# Hydrogen_Rocket.net
KiCad netlist of a schematic drawn in EasyEDA
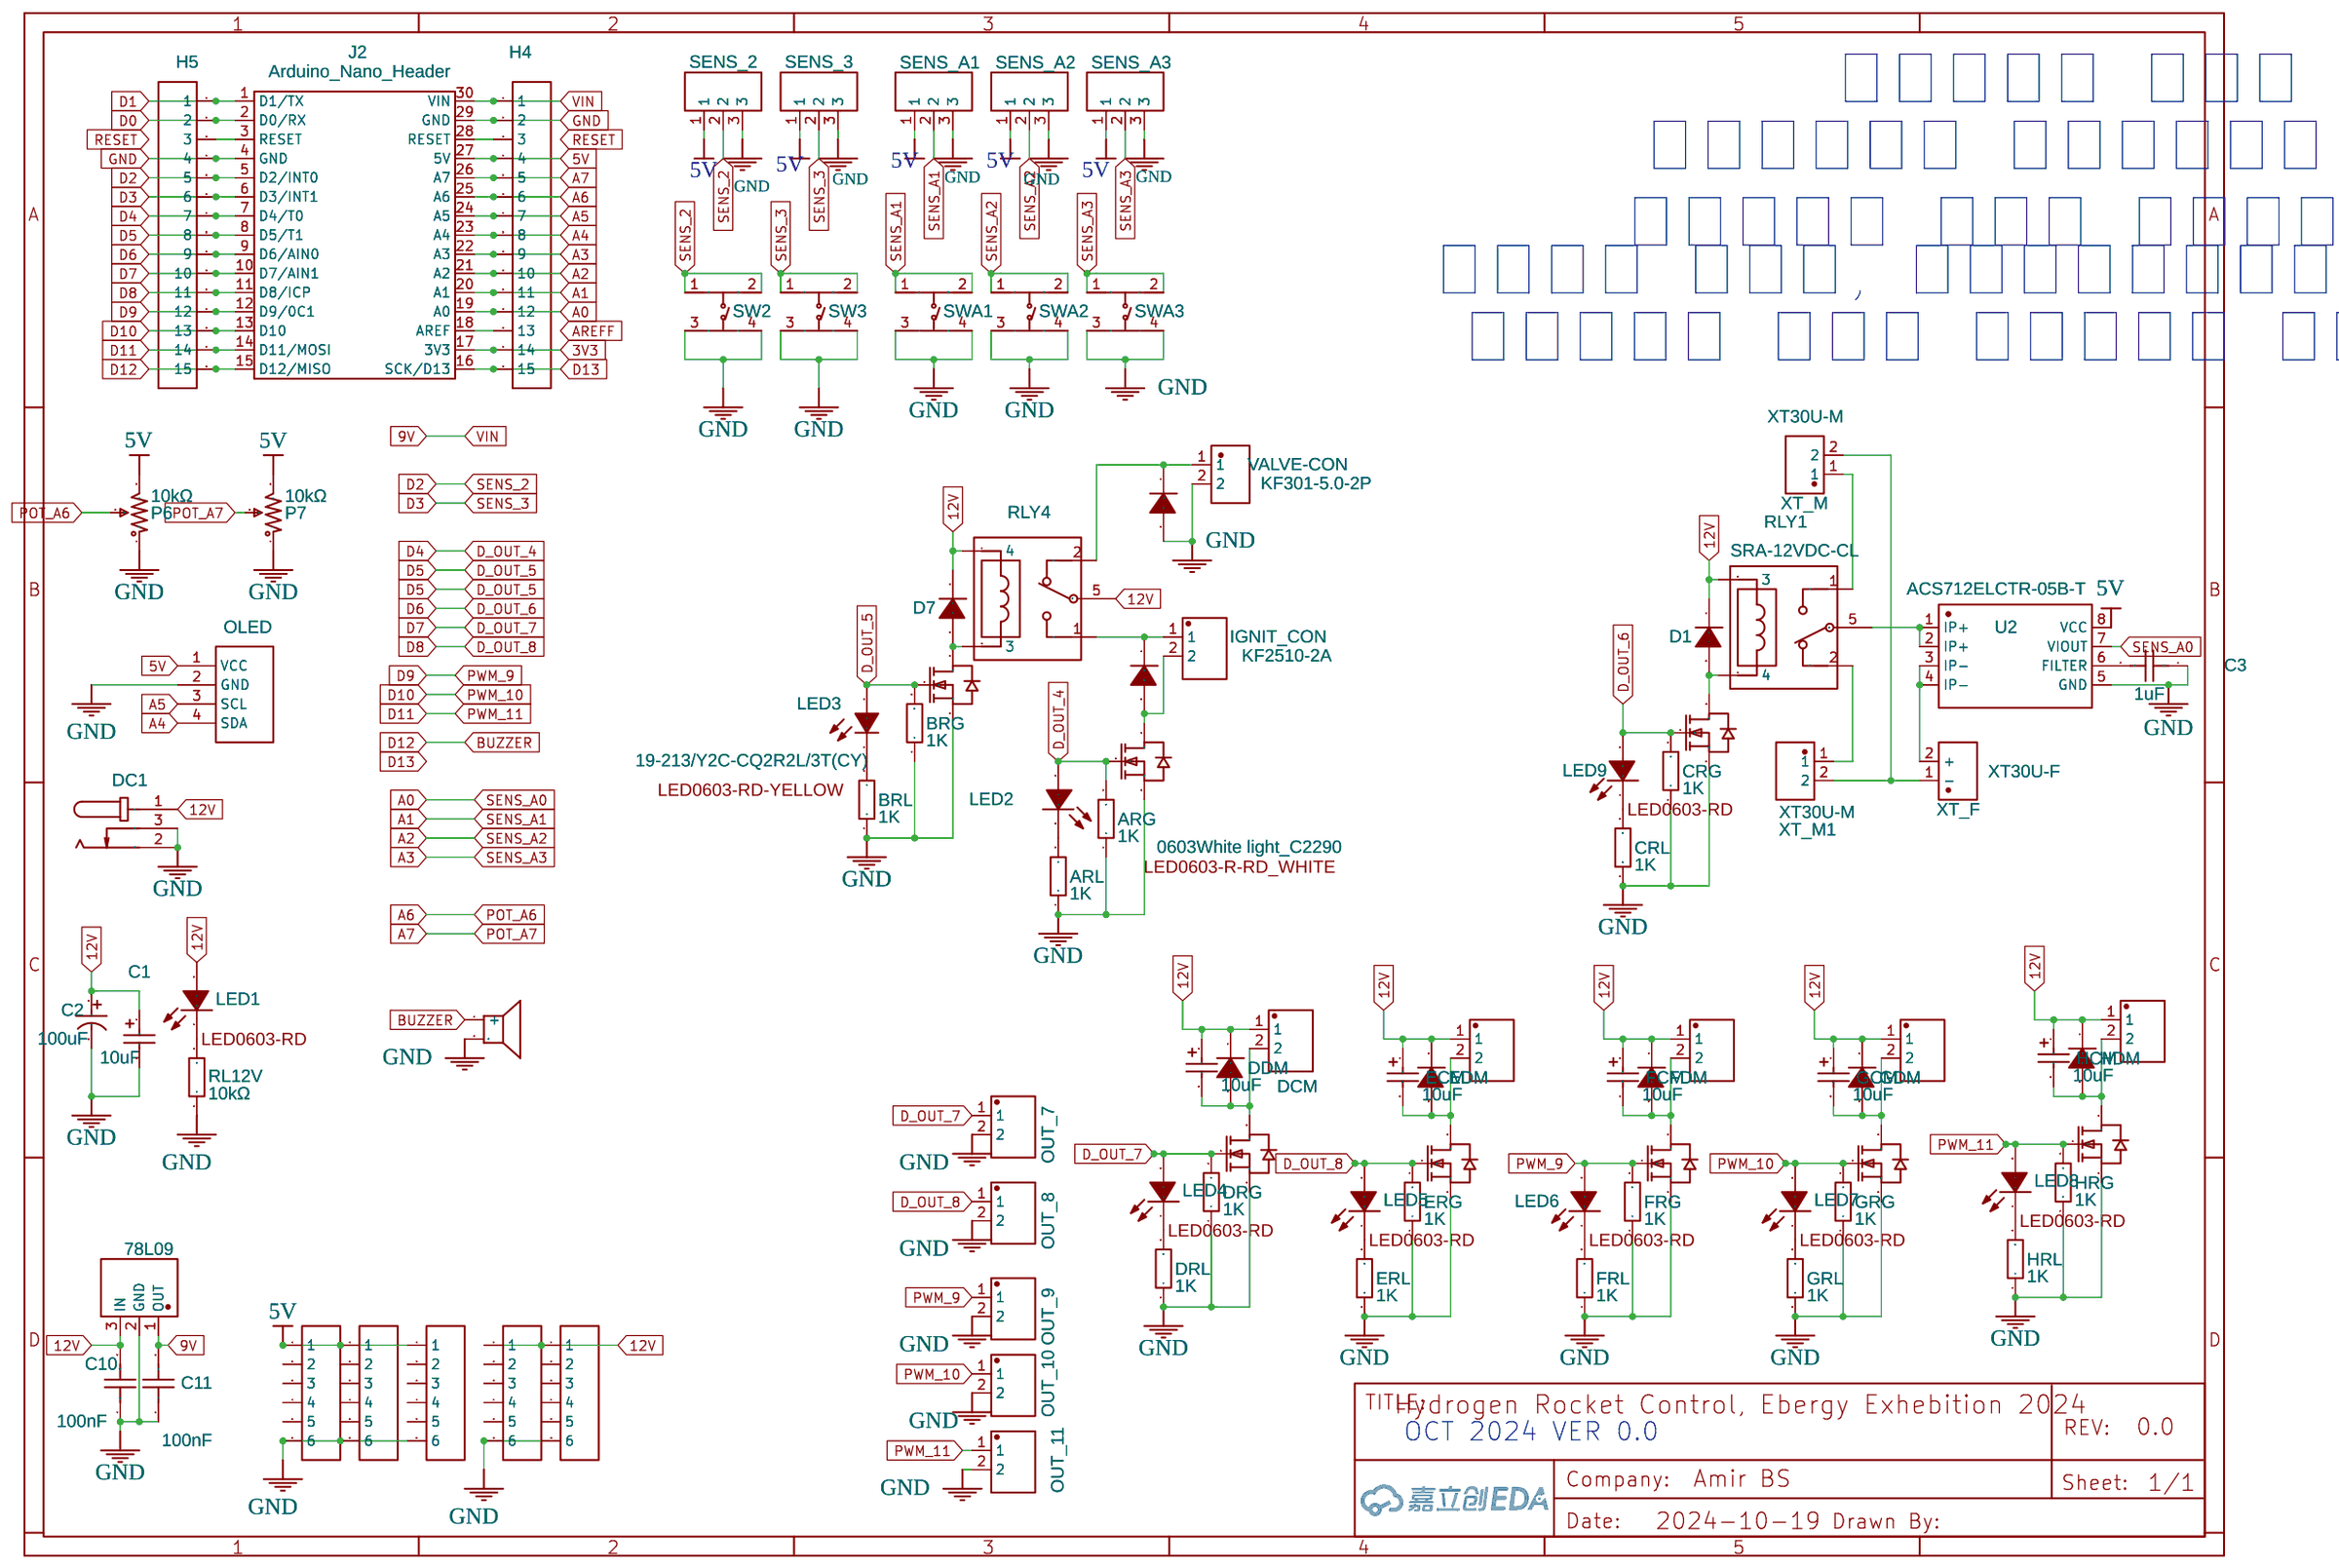
[diagram p0: schematic sheet]

(export (version "E")
  (design (tool "Eeschema 10.0.6"))
  (components
    (comp (ref "AQ")
      (value "Q")
      (fields (field (name "BOM_Manufacturer Part") "AO3400") (field (name "BOM_Supplier Part") "C5224189"))
      (libsource (lib "") (part "JSM2302_4"))
    )
    (comp (ref "ARG")
      (value "1K")
      (fields
        (field (name "BOM_Manufacturer Part") "0603WAF1001T5E")
        (field (name "BOM_Supplier Part") "C21190")
      )
      (libsource (lib "") (part "0603WAF1001T5E_7"))
    )
    (comp (ref "ARL")
      (value "1K")
      (fields
        (field (name "BOM_Manufacturer Part") "0603WAF1001T5E")
        (field (name "BOM_Supplier Part") "C21190")
      )
      (libsource (lib "") (part "0603WAF1001T5E_15"))
    )
    (comp (ref "BQ")
      (value "Q")
      (fields (field (name "BOM_Manufacturer Part") "AO3400") (field (name "BOM_Supplier Part") "C5224189"))
      (libsource (lib "") (part "JSM2302_6"))
    )
    (comp (ref "BRG")
      (value "1K")
      (fields
        (field (name "BOM_Manufacturer Part") "0603WAF1001T5E")
        (field (name "BOM_Supplier Part") "C21190")
      )
      (libsource (lib "") (part "0603WAF1001T5E_2"))
    )
    (comp (ref "BRL")
      (value "1K")
      (fields
        (field (name "BOM_Manufacturer Part") "0603WAF1001T5E")
        (field (name "BOM_Supplier Part") "C21190")
      )
      (libsource (lib "") (part "0603WAF1001T5E_11"))
    )
    (comp (ref "BUZZER1")
      (value "BUZZER-12X9")
      (fields (field (name "Manufacturer Part") "buzzer-12X9"))
      (libsource (lib "") (part "BUZZER-12X9"))
    )
    (comp (ref "C1")
      (value "10uF")
      (fields (field (name "Manufacturer Part") "TAJA106K016RNJ") (field (name "Manufacturer") "Kyocera AVX"))
      (libsource (lib "") (part "TAJA106K016RNJ_4"))
    )
    (comp (ref "C2")
      (value "100uF")
      (fields
        (field (name "Manufacturer Part") "KM107M035E11RR0VH2FP0")
        (field (name "Manufacturer") "CX(承兴)")
      )
      (libsource (lib "") (part "100uF 35V 6.3*11"))
    )
    (comp (ref "C3")
      (value "1uF")
      (fields
        (field (name "Manufacturer Part") "CL10A105KB8NNNC")
        (field (name "Manufacturer") "SAMSUNG(三星)")
      )
      (libsource (lib "") (part "CL10A105KB8NNNC"))
    )
    (comp (ref "C10")
      (value "100nF")
      (fields
        (field (name "Manufacturer Part") "CC0603KRX7R9BB104")
        (field (name "Manufacturer") "YAGEO(国巨)")
      )
      (libsource (lib "") (part "CC0603KRX7R9BB104"))
    )
    (comp (ref "C11")
      (value "100nF")
      (fields
        (field (name "Manufacturer Part") "CC0603KRX7R9BB104")
        (field (name "Manufacturer") "YAGEO(国巨)")
      )
      (libsource (lib "") (part "CC0603KRX7R9BB104"))
    )
    (comp (ref "CQ")
      (value "Q")
      (fields (field (name "BOM_Manufacturer Part") "AO3400") (field (name "BOM_Supplier Part") "C5224189"))
      (libsource (lib "") (part "JSM2302_3"))
    )
    (comp (ref "CRG")
      (value "1K")
      (fields
        (field (name "BOM_Manufacturer Part") "0603WAF1001T5E")
        (field (name "BOM_Supplier Part") "C21190")
      )
      (libsource (lib "") (part "0603WAF1001T5E_10"))
    )
    (comp (ref "CRL")
      (value "1K")
      (fields
        (field (name "BOM_Manufacturer Part") "0603WAF1001T5E")
        (field (name "BOM_Supplier Part") "C21190")
      )
      (libsource (lib "") (part "0603WAF1001T5E_3"))
    )
    (comp (ref "D1")
      (value "M7_C95872")
      (fields (field (name "Manufacturer Part") "M7") (field (name "Manufacturer") "MDD"))
      (libsource (lib "") (part "M7_C95872"))
    )
    (comp (ref "D7")
      (value "M7_C95872")
      (fields (field (name "Manufacturer Part") "M7") (field (name "Manufacturer") "MDD"))
      (libsource (lib "") (part "M7_C95872"))
    )
    (comp (ref "DC1")
      (value "DC")
      (fields
        (field (name "BOM_Manufacturer Part") "DC005-2.0MM")
        (field (name "BOM_Supplier Part") "C111567")
      )
      (libsource (lib "") (part "DC005-2.0MM"))
    )
    (comp (ref "DCM")
      (value "10uF")
      (fields (field (name "Manufacturer Part") "TAJA106K016RNJ") (field (name "Manufacturer") "Kyocera AVX"))
      (libsource (lib "") (part "TAJA106K016RNJ_5"))
    )
    (comp (ref "DCON")
      (value "KF2510-2A")
      (fields (field (name "BOM_Supplier Part") "C27543"))
      (libsource (lib "") (part "KF2510-2A_6"))
    )
    (comp (ref "DDM")
      (value "1N4007")
      (fields (field (name "BOM_Manufacturer Part") "1N4007F") (field (name "BOM_Supplier Part") "C110856"))
      (libsource (lib "") (part "1N4007F_3"))
    )
    (comp (ref "DDM1")
      (value "1N4007")
      (fields (field (name "BOM_Manufacturer Part") "1N4007F") (field (name "BOM_Supplier Part") "C110856"))
      (libsource (lib "") (part "1N4007F_3"))
    )
    (comp (ref "DDM2")
      (value "1N4007")
      (fields (field (name "BOM_Manufacturer Part") "1N4007F") (field (name "BOM_Supplier Part") "C110856"))
      (libsource (lib "") (part "1N4007F_3"))
    )
    (comp (ref "DQ")
      (value "Q")
      (fields (field (name "BOM_Manufacturer Part") "AO3400") (field (name "BOM_Supplier Part") "C5224189"))
      (libsource (lib "") (part "JSM2302_2"))
    )
    (comp (ref "DRG")
      (value "1K")
      (fields
        (field (name "BOM_Manufacturer Part") "0603WAF1001T5E")
        (field (name "BOM_Supplier Part") "C21190")
      )
      (libsource (lib "") (part "0603WAF1001T5E_6"))
    )
    (comp (ref "DRL")
      (value "1K")
      (fields
        (field (name "BOM_Manufacturer Part") "0603WAF1001T5E")
        (field (name "BOM_Supplier Part") "C21190")
      )
      (libsource (lib "") (part "0603WAF1001T5E_14"))
    )
    (comp (ref "ECM")
      (value "10uF")
      (fields (field (name "Manufacturer Part") "TAJA106K016RNJ") (field (name "Manufacturer") "Kyocera AVX"))
      (libsource (lib "") (part "TAJA106K016RNJ"))
    )
    (comp (ref "ECON")
      (value "KF2510-2A")
      (fields (field (name "BOM_Supplier Part") "C27543"))
      (libsource (lib "") (part "KF2510-2A_2"))
    )
    (comp (ref "EDM")
      (value "1N4007")
      (fields (field (name "BOM_Manufacturer Part") "1N4007F") (field (name "BOM_Supplier Part") "C110856"))
      (libsource (lib "") (part "1N4007F_2"))
    )
    (comp (ref "EQ")
      (value "Q")
      (fields (field (name "BOM_Manufacturer Part") "AO3400") (field (name "BOM_Supplier Part") "C5224189"))
      (libsource (lib "") (part "JSM2302"))
    )
    (comp (ref "ERG")
      (value "1K")
      (fields
        (field (name "BOM_Manufacturer Part") "0603WAF1001T5E")
        (field (name "BOM_Supplier Part") "C21190")
      )
      (libsource (lib "") (part "0603WAF1001T5E_9"))
    )
    (comp (ref "ERL")
      (value "1K")
      (fields
        (field (name "BOM_Manufacturer Part") "0603WAF1001T5E")
        (field (name "BOM_Supplier Part") "C21190")
      )
      (libsource (lib "") (part "0603WAF1001T5E"))
    )
    (comp (ref "FCM")
      (value "10uF")
      (fields (field (name "Manufacturer Part") "TAJA106K016RNJ") (field (name "Manufacturer") "Kyocera AVX"))
      (libsource (lib "") (part "TAJA106K016RNJ_1"))
    )
    (comp (ref "FCON")
      (value "KF2510-2A")
      (fields (field (name "BOM_Supplier Part") "C27543"))
      (libsource (lib "") (part "KF2510-2A_4"))
    )
    (comp (ref "FDM")
      (value "1N4007")
      (fields (field (name "BOM_Manufacturer Part") "1N4007F") (field (name "BOM_Supplier Part") "C110856"))
      (libsource (lib "") (part "1N4007F_4"))
    )
    (comp (ref "FQ")
      (value "Q")
      (fields (field (name "BOM_Manufacturer Part") "AO3400") (field (name "BOM_Supplier Part") "C5224189"))
      (libsource (lib "") (part "JSM2302_7"))
    )
    (comp (ref "FRG")
      (value "1K")
      (fields
        (field (name "BOM_Manufacturer Part") "0603WAF1001T5E")
        (field (name "BOM_Supplier Part") "C21190")
      )
      (libsource (lib "") (part "0603WAF1001T5E_13"))
    )
    (comp (ref "FRL")
      (value "1K")
      (fields
        (field (name "BOM_Manufacturer Part") "0603WAF1001T5E")
        (field (name "BOM_Supplier Part") "C21190")
      )
      (libsource (lib "") (part "0603WAF1001T5E_5"))
    )
    (comp (ref "GCM")
      (value "10uF")
      (fields (field (name "Manufacturer Part") "TAJA106K016RNJ") (field (name "Manufacturer") "Kyocera AVX"))
      (libsource (lib "") (part "TAJA106K016RNJ_3"))
    )
    (comp (ref "GCON")
      (value "KF2510-2A")
      (fields (field (name "BOM_Supplier Part") "C27543"))
      (libsource (lib "") (part "KF2510-2A_3"))
    )
    (comp (ref "GDM")
      (value "1N4007")
      (fields (field (name "BOM_Manufacturer Part") "1N4007F") (field (name "BOM_Supplier Part") "C110856"))
      (libsource (lib "") (part "1N4007F"))
    )
    (comp (ref "GQ")
      (value "Q")
      (fields (field (name "BOM_Manufacturer Part") "AO3400") (field (name "BOM_Supplier Part") "C5224189"))
      (libsource (lib "") (part "JSM2302_1"))
    )
    (comp (ref "GRG")
      (value "1K")
      (fields
        (field (name "BOM_Manufacturer Part") "0603WAF1001T5E")
        (field (name "BOM_Supplier Part") "C21190")
      )
      (libsource (lib "") (part "0603WAF1001T5E_8"))
    )
    (comp (ref "GRL")
      (value "1K")
      (fields
        (field (name "BOM_Manufacturer Part") "0603WAF1001T5E")
        (field (name "BOM_Supplier Part") "C21190")
      )
      (libsource (lib "") (part "0603WAF1001T5E_4"))
    )
    (comp (ref "H1")
      (value "HDR-F-2.54_1x6")
      (fields (field (name "BOM_Supplier Part") "C40877"))
      (libsource (lib "") (part "HDR-F-2.54_1x6"))
    )
    (comp (ref "H2")
      (value "HDR-F-2.54_1x6")
      (fields (field (name "BOM_Supplier Part") "C40877"))
      (libsource (lib "") (part "HDR-F-2.54_1x6"))
    )
    (comp (ref "H3")
      (value "HDR-F-2.54_1x6")
      (fields (field (name "BOM_Supplier Part") "C40877"))
      (libsource (lib "") (part "HDR-F-2.54_1x6"))
    )
    (comp (ref "H4")
      (value "HDR-F-2.54_1x15")
      (fields (field (name "BOM_Supplier Part") "C124408"))
      (libsource (lib "") (part "HDR-F-2.54_1x15_1"))
    )
    (comp (ref "H5")
      (value "HDR-F-2.54_1x15")
      (fields (field (name "BOM_Supplier Part") "C124408"))
      (libsource (lib "") (part "HDR-F-2.54_1x15"))
    )
    (comp (ref "H6")
      (value "HDR-F-2.54_1x6")
      (fields (field (name "BOM_Supplier Part") "C40877"))
      (libsource (lib "") (part "HDR-F-2.54_1x6"))
    )
    (comp (ref "H11")
      (value "HDR-F-2.54_1x6")
      (fields (field (name "BOM_Supplier Part") "C40877"))
      (libsource (lib "") (part "HDR-F-2.54_1x6"))
    )
    (comp (ref "HCM")
      (value "10uF")
      (fields (field (name "Manufacturer Part") "TAJA106K016RNJ") (field (name "Manufacturer") "Kyocera AVX"))
      (libsource (lib "") (part "TAJA106K016RNJ_2"))
    )
    (comp (ref "HCON")
      (value "KF2510-2A")
      (fields (field (name "BOM_Supplier Part") "C27543"))
      (libsource (lib "") (part "KF2510-2A_5"))
    )
    (comp (ref "HDM")
      (value "1N4007")
      (fields (field (name "BOM_Manufacturer Part") "1N4007F") (field (name "BOM_Supplier Part") "C110856"))
      (libsource (lib "") (part "1N4007F_1"))
    )
    (comp (ref "HQ")
      (value "Q")
      (fields (field (name "BOM_Manufacturer Part") "AO3400") (field (name "BOM_Supplier Part") "C5224189"))
      (libsource (lib "") (part "JSM2302_5"))
    )
    (comp (ref "HRG")
      (value "1K")
      (fields
        (field (name "BOM_Manufacturer Part") "0603WAF1001T5E")
        (field (name "BOM_Supplier Part") "C21190")
      )
      (libsource (lib "") (part "0603WAF1001T5E_12"))
    )
    (comp (ref "HRL")
      (value "1K")
      (fields
        (field (name "BOM_Manufacturer Part") "0603WAF1001T5E")
        (field (name "BOM_Supplier Part") "C21190")
      )
      (libsource (lib "") (part "0603WAF1001T5E_1"))
    )
    (comp (ref "IGNIT_CON")
      (value "KF2510-2A")
      (fields (field (name "BOM_Supplier Part") "C27543"))
      (libsource (lib "") (part "KF2510-2A_1"))
    )
    (comp (ref "J2") (value "Arduino_Nano_Header") (libsource (lib "") (part "Arduino_Nano_Header")))
    (comp (ref "LED1")
      (value "KT-0603R")
      (fields (field (name "Manufacturer") "KENTO"))
      (libsource (lib "") (part "KT-0603R"))
    )
    (comp (ref "LED2")
      (value "0603White light_C2290")
      (fields (field (name "Manufacturer Part") "KT-0603W") (field (name "Manufacturer") "KENTO"))
      (libsource (lib "") (part "0603White light_C2290"))
    )
    (comp (ref "LED3")
      (value "19-213/Y2C-CQ2R2L/3T(CY)")
      (fields (field (name "Manufacturer") "EVERLIGHT(亿光)"))
      (libsource (lib "") (part "19-213/Y2C-CQ2R2L/3T(CY)"))
    )
    (comp (ref "LED4")
      (value "KT-0603R")
      (fields (field (name "Manufacturer") "KENTO"))
      (libsource (lib "") (part "KT-0603R"))
    )
    (comp (ref "LED5")
      (value "KT-0603R")
      (fields (field (name "Manufacturer") "KENTO"))
      (libsource (lib "") (part "KT-0603R"))
    )
    (comp (ref "LED6")
      (value "KT-0603R")
      (fields (field (name "Manufacturer") "KENTO"))
      (libsource (lib "") (part "KT-0603R"))
    )
    (comp (ref "LED7")
      (value "KT-0603R")
      (fields (field (name "Manufacturer") "KENTO"))
      (libsource (lib "") (part "KT-0603R"))
    )
    (comp (ref "LED8")
      (value "KT-0603R")
      (fields (field (name "Manufacturer") "KENTO"))
      (libsource (lib "") (part "KT-0603R"))
    )
    (comp (ref "LED9")
      (value "KT-0603R")
      (fields (field (name "Manufacturer") "KENTO"))
      (libsource (lib "") (part "KT-0603R"))
    )
    (comp (ref "OLED")
      (value "1.3 inch OLED SSH1106 I2C 128x64 copy")
      (libsource (lib "") (part "1.3 inch OLED SSH1106 I2C 128x64 copy"))
    )
    (comp (ref "OUT_7")
      (value "KF2510-2A")
      (fields (field (name "BOM_Supplier Part") "C27543"))
      (libsource (lib "") (part "KF2510-2A"))
    )
    (comp (ref "OUT_8")
      (value "KF2510-2A")
      (fields (field (name "BOM_Supplier Part") "C27543"))
      (libsource (lib "") (part "KF2510-2A"))
    )
    (comp (ref "OUT_9")
      (value "KF2510-2A")
      (fields (field (name "BOM_Supplier Part") "C27543"))
      (libsource (lib "") (part "KF2510-2A"))
    )
    (comp (ref "OUT_10")
      (value "KF2510-2A")
      (fields (field (name "BOM_Supplier Part") "C27543"))
      (libsource (lib "") (part "KF2510-2A"))
    )
    (comp (ref "OUT_11")
      (value "KF2510-2A")
      (fields (field (name "BOM_Supplier Part") "C27543"))
      (libsource (lib "") (part "KF2510-2A"))
    )
    (comp (ref "P6")
      (value "10kΩ")
      (fields (field (name "Manufacturer Part") "3296W-1-103") (field (name "Manufacturer") "BOCHEN(博晨)"))
      (libsource (lib "") (part "3296W-1-103"))
    )
    (comp (ref "P7")
      (value "10kΩ")
      (fields (field (name "Manufacturer Part") "3296W-1-103") (field (name "Manufacturer") "BOCHEN(博晨)"))
      (libsource (lib "") (part "3296W-1-103"))
    )
    (comp (ref "RL12V")
      (value "10kΩ")
      (fields
        (field (name "BOM_Manufacturer Part") "0603WAF1002T5E")
        (field (name "BOM_Supplier Part") "C25804")
      )
      (libsource (lib "") (part "0603WAF1002T5E"))
    )
    (comp (ref "RLY1")
      (value "SRA-12VDC-CL")
      (fields (field (name "Manufacturer") "松乐"))
      (libsource (lib "") (part "SRA-12VDC-CL_1"))
    )
    (comp (ref "RLY4")
      (value "SRA-12VDC-CL")
      (fields (field (name "Manufacturer") "松乐"))
      (libsource (lib "") (part "SRA-12VDC-CL"))
    )
    (comp (ref "SENS_2")
      (value "FK2510")
      (fields (field (name "Manufacturer Part") "2510-3A") (field (name "Manufacturer") "BOOMELE(博穆精密)"))
      (libsource (lib "") (part "kf2510_3A_1"))
    )
    (comp (ref "SENS_3")
      (value "FK2510")
      (fields (field (name "Manufacturer Part") "2510-3A") (field (name "Manufacturer") "BOOMELE(博穆精密)"))
      (libsource (lib "") (part "kf2510_3A_1"))
    )
    (comp (ref "SENS_A1")
      (value "FK2510")
      (fields (field (name "Manufacturer Part") "2510-3A") (field (name "Manufacturer") "BOOMELE(博穆精密)"))
      (libsource (lib "") (part "kf2510_3A"))
    )
    (comp (ref "SENS_A2")
      (value "FK2510")
      (fields (field (name "Manufacturer Part") "2510-3A") (field (name "Manufacturer") "BOOMELE(博穆精密)"))
      (libsource (lib "") (part "kf2510_3A"))
    )
    (comp (ref "SENS_A3")
      (value "FK2510")
      (fields (field (name "Manufacturer Part") "2510-3A") (field (name "Manufacturer") "BOOMELE(博穆精密)"))
      (libsource (lib "") (part "kf2510_3A"))
    )
    (comp (ref "SW2")
      (value "TC-6610-7-160G")
      (fields (field (name "Manufacturer") "HCTL(华灿天禄)"))
      (libsource (lib "") (part "TC-6610-7-160G_1"))
    )
    (comp (ref "SW3")
      (value "TC-6610-7-160G")
      (fields (field (name "Manufacturer") "HCTL(华灿天禄)"))
      (libsource (lib "") (part "TC-6610-7-160G_1"))
    )
    (comp (ref "SWA1")
      (value "TC-6610-7-160G")
      (fields (field (name "Manufacturer") "HCTL(华灿天禄)"))
      (libsource (lib "") (part "TC-6610-7-160G"))
    )
    (comp (ref "SWA2")
      (value "TC-6610-7-160G")
      (fields (field (name "Manufacturer") "HCTL(华灿天禄)"))
      (libsource (lib "") (part "TC-6610-7-160G"))
    )
    (comp (ref "SWA3")
      (value "TC-6610-7-160G")
      (fields (field (name "Manufacturer") "HCTL(华灿天禄)"))
      (libsource (lib "") (part "TC-6610-7-160G"))
    )
    (comp (ref "U2")
      (value "ACS712ELCTR-05B-T")
      (fields (field (name "Manufacturer") "ALLEGRO(美国埃戈罗)"))
      (libsource (lib "") (part "ACS712ELCTR-05B-T"))
    )
    (comp (ref "U5")
      (value "78L09")
      (fields (field (name "Manufacturer Part") "78L09U 78L09") (field (name "Manufacturer") "CBI(创基)"))
      (libsource (lib "") (part "78L09U 78L09"))
    )
    (comp (ref "VALVE-CON")
      (value "KF301-5.0-2P")
      (fields (field (name "Manufacturer") "KEFA(科发)"))
      (libsource (lib "") (part "KF301-5.0-2P"))
    )
    (comp (ref "XT_F")
      (value "XT30U-F")
      (fields (field (name "Manufacturer") "AMASS(艾迈斯)"))
      (libsource (lib "") (part "XT30U-F"))
    )
    (comp (ref "XT_M")
      (value "XT30U-M")
      (fields (field (name "Manufacturer") "AMASS(艾迈斯)"))
      (libsource (lib "") (part "XT30U-M"))
    )
    (comp (ref "XT_M1")
      (value "XT30U-M")
      (fields (field (name "Manufacturer") "AMASS(艾迈斯)"))
      (libsource (lib "") (part "XT30U-M_1"))
    )
  )
  (nets
    (net (code "1") (name "3V3") (class "Default")
      (node (ref "H4") (pin "14") (pinfunction "14_14") (pintype "unspecified"))
      (node (ref "J2") (pin "17") (pinfunction "3V3_17") (pintype "unspecified"))
    )
    (net (code "2") (name "5V") (class "Default")
      (node (ref "H1") (pin "1") (pinfunction "1_1") (pintype "input"))
      (node (ref "H2") (pin "1") (pinfunction "1_1") (pintype "input"))
      (node (ref "H3") (pin "1") (pinfunction "1_1") (pintype "input"))
      (node (ref "H4") (pin "4") (pinfunction "4_4") (pintype "unspecified"))
      (node (ref "J2") (pin "27") (pinfunction "5V_27") (pintype "unspecified"))
      (node (ref "OLED") (pin "1") (pinfunction "VCC_1") (pintype "passive"))
      (node (ref "P6") (pin "3") (pinfunction "3_3") (pintype "unspecified"))
      (node (ref "P7") (pin "3") (pinfunction "3_3") (pintype "unspecified"))
      (node (ref "SENS_2") (pin "1") (pinfunction "1_1") (pintype "unspecified"))
      (node (ref "SENS_3") (pin "1") (pinfunction "1_1") (pintype "unspecified"))
      (node (ref "SENS_A1") (pin "1") (pinfunction "1_1") (pintype "unspecified"))
      (node (ref "SENS_A2") (pin "1") (pinfunction "1_1") (pintype "unspecified"))
      (node (ref "SENS_A3") (pin "1") (pinfunction "1_1") (pintype "unspecified"))
      (node (ref "U2") (pin "8") (pinfunction "VCC_8") (pintype "unspecified"))
    )
    (net (code "3") (name "9V") (class "Default")
      (node (ref "C11") (pin "2") (pinfunction "2_2") (pintype "unspecified"))
      (node (ref "H4") (pin "1") (pinfunction "1_1") (pintype "unspecified"))
      (node (ref "J2") (pin "30") (pinfunction "VIN_30") (pintype "unspecified"))
      (node (ref "U5") (pin "1") (pinfunction "OUT_1") (pintype "unspecified"))
    )
    (net (code "4") (name "12V") (class "Default")
      (node (ref "C1") (pin "1") (pinfunction "1_1") (pintype "input"))
      (node (ref "C10") (pin "2") (pinfunction "2_2") (pintype "unspecified"))
      (node (ref "C2") (pin "1") (pinfunction "1_1") (pintype "input"))
      (node (ref "D1") (pin "1") (pinfunction "K_1") (pintype "unspecified"))
      (node (ref "D7") (pin "1") (pinfunction "K_1") (pintype "unspecified"))
      (node (ref "DC1") (pin "1") (pinfunction "1_1") (pintype "unspecified"))
      (node (ref "DCM") (pin "1") (pinfunction "1_1") (pintype "input"))
      (node (ref "DCON") (pin "1") (pinfunction "1_1") (pintype "unspecified"))
      (node (ref "DDM") (pin "1") (pinfunction "C_1") (pintype "unspecified"))
      (node (ref "ECM") (pin "1") (pinfunction "1_1") (pintype "input"))
      (node (ref "ECON") (pin "1") (pinfunction "1_1") (pintype "unspecified"))
      (node (ref "EDM") (pin "1") (pinfunction "C_1") (pintype "unspecified"))
      (node (ref "FCM") (pin "1") (pinfunction "1_1") (pintype "input"))
      (node (ref "FCON") (pin "1") (pinfunction "1_1") (pintype "unspecified"))
      (node (ref "FDM") (pin "1") (pinfunction "C_1") (pintype "unspecified"))
      (node (ref "GCM") (pin "1") (pinfunction "1_1") (pintype "input"))
      (node (ref "GCON") (pin "1") (pinfunction "1_1") (pintype "unspecified"))
      (node (ref "GDM") (pin "1") (pinfunction "C_1") (pintype "unspecified"))
      (node (ref "H11") (pin "1") (pinfunction "1_1") (pintype "input"))
      (node (ref "H6") (pin "1") (pinfunction "1_1") (pintype "input"))
      (node (ref "HCM") (pin "1") (pinfunction "1_1") (pintype "input"))
      (node (ref "HCON") (pin "1") (pinfunction "1_1") (pintype "unspecified"))
      (node (ref "HDM") (pin "1") (pinfunction "C_1") (pintype "unspecified"))
      (node (ref "LED1") (pin "2") (pinfunction "A_2") (pintype "unspecified"))
      (node (ref "RLY1") (pin "3") (pinfunction "3_3") (pintype "unspecified"))
      (node (ref "RLY4") (pin "4") (pinfunction "4_4") (pintype "unspecified"))
      (node (ref "RLY4") (pin "5") (pinfunction "5_5") (pintype "unspecified"))
      (node (ref "U5") (pin "3") (pinfunction "IN_3") (pintype "unspecified"))
    )
    (net (code "5") (name "A0") (class "Default")
      (node (ref "H4") (pin "12") (pinfunction "12_12") (pintype "unspecified"))
      (node (ref "J2") (pin "19") (pinfunction "A0_19") (pintype "unspecified"))
      (node (ref "U2") (pin "7") (pinfunction "VIOUT_7") (pintype "unspecified"))
    )
    (net (code "6") (name "A1") (class "Default")
      (node (ref "H4") (pin "11") (pinfunction "11_11") (pintype "unspecified"))
      (node (ref "J2") (pin "20") (pinfunction "A1_20") (pintype "unspecified"))
      (node (ref "SENS_A1") (pin "2") (pinfunction "2_2") (pintype "unspecified"))
      (node (ref "SWA1") (pin "1") (pinfunction "1_1") (pintype "unspecified"))
      (node (ref "SWA1") (pin "2") (pinfunction "2_2") (pintype "unspecified"))
    )
    (net (code "7") (name "A2") (class "Default")
      (node (ref "H4") (pin "10") (pinfunction "10_10") (pintype "unspecified"))
      (node (ref "J2") (pin "21") (pinfunction "A2_21") (pintype "unspecified"))
      (node (ref "SENS_A2") (pin "2") (pinfunction "2_2") (pintype "unspecified"))
      (node (ref "SWA2") (pin "1") (pinfunction "1_1") (pintype "unspecified"))
      (node (ref "SWA2") (pin "2") (pinfunction "2_2") (pintype "unspecified"))
    )
    (net (code "8") (name "A3") (class "Default")
      (node (ref "H4") (pin "9") (pinfunction "9_9") (pintype "unspecified"))
      (node (ref "J2") (pin "22") (pinfunction "A3_22") (pintype "unspecified"))
      (node (ref "SENS_A3") (pin "2") (pinfunction "2_2") (pintype "unspecified"))
      (node (ref "SWA3") (pin "1") (pinfunction "1_1") (pintype "unspecified"))
      (node (ref "SWA3") (pin "2") (pinfunction "2_2") (pintype "unspecified"))
    )
    (net (code "9") (name "A4") (class "Default")
      (node (ref "H4") (pin "8") (pinfunction "8_8") (pintype "unspecified"))
      (node (ref "J2") (pin "23") (pinfunction "A4_23") (pintype "unspecified"))
      (node (ref "OLED") (pin "4") (pinfunction "SDA_4") (pintype "bidirectional"))
    )
    (net (code "10") (name "A5") (class "Default")
      (node (ref "H4") (pin "7") (pinfunction "7_7") (pintype "unspecified"))
      (node (ref "J2") (pin "24") (pinfunction "A5_24") (pintype "unspecified"))
      (node (ref "OLED") (pin "3") (pinfunction "SCL_3") (pintype "bidirectional"))
    )
    (net (code "11") (name "A6") (class "Default")
      (node (ref "H4") (pin "6") (pinfunction "6_6") (pintype "unspecified"))
      (node (ref "J2") (pin "25") (pinfunction "A6_25") (pintype "unspecified"))
      (node (ref "P6") (pin "2") (pinfunction "2_2") (pintype "unspecified"))
    )
    (net (code "12") (name "A7") (class "Default")
      (node (ref "H4") (pin "5") (pinfunction "5_5") (pintype "unspecified"))
      (node (ref "J2") (pin "26") (pinfunction "A7_26") (pintype "unspecified"))
      (node (ref "P7") (pin "2") (pinfunction "2_2") (pintype "unspecified"))
    )
    (net (code "14") (name "BUZZER") (class "Default")
      (node (ref "BUZZER1") (pin "1") (pinfunction "+_1") (pintype "unspecified"))
      (node (ref "H5") (pin "15") (pinfunction "15_15") (pintype "unspecified"))
      (node (ref "J2") (pin "15") (pinfunction "D12/MISO_15") (pintype "unspecified"))
    )
    (net (code "15") (name "D0") (class "Default")
      (node (ref "H5") (pin "2") (pinfunction "2_2") (pintype "unspecified"))
      (node (ref "J2") (pin "2") (pinfunction "D0/RX_2") (pintype "unspecified"))
    )
    (net (code "16") (name "D1") (class "Default")
      (node (ref "H5") (pin "1") (pinfunction "1_1") (pintype "unspecified"))
      (node (ref "J2") (pin "1") (pinfunction "D1/TX_1") (pintype "unspecified"))
    )
    (net (code "17") (name "D2") (class "Default")
      (node (ref "H5") (pin "5") (pinfunction "5_5") (pintype "unspecified"))
      (node (ref "J2") (pin "5") (pinfunction "D2/INT0_5") (pintype "unspecified"))
      (node (ref "SENS_2") (pin "2") (pinfunction "2_2") (pintype "unspecified"))
      (node (ref "SW2") (pin "1") (pinfunction "1_1") (pintype "unspecified"))
      (node (ref "SW2") (pin "2") (pinfunction "2_2") (pintype "unspecified"))
    )
    (net (code "18") (name "D3") (class "Default")
      (node (ref "H5") (pin "6") (pinfunction "6_6") (pintype "unspecified"))
      (node (ref "J2") (pin "6") (pinfunction "D3/INT1_6") (pintype "unspecified"))
      (node (ref "SENS_3") (pin "2") (pinfunction "2_2") (pintype "unspecified"))
      (node (ref "SW3") (pin "1") (pinfunction "1_1") (pintype "unspecified"))
      (node (ref "SW3") (pin "2") (pinfunction "2_2") (pintype "unspecified"))
    )
    (net (code "19") (name "D4") (class "Default")
      (node (ref "AQ") (pin "1") (pinfunction "G_1") (pintype "unspecified"))
      (node (ref "ARG") (pin "2") (pinfunction "2_2") (pintype "input"))
      (node (ref "H5") (pin "7") (pinfunction "7_7") (pintype "unspecified"))
      (node (ref "J2") (pin "7") (pinfunction "D4/T0_7") (pintype "unspecified"))
      (node (ref "LED2") (pin "1") (pinfunction "A_1") (pintype "unspecified"))
    )
    (net (code "20") (name "D5") (class "Default")
      (node (ref "BQ") (pin "1") (pinfunction "G_1") (pintype "unspecified"))
      (node (ref "BRG") (pin "2") (pinfunction "2_2") (pintype "input"))
      (node (ref "H5") (pin "8") (pinfunction "8_8") (pintype "unspecified"))
      (node (ref "J2") (pin "8") (pinfunction "D5/T1_8") (pintype "unspecified"))
      (node (ref "LED3") (pin "2") (pinfunction "A_2") (pintype "input"))
    )
    (net (code "21") (name "D6") (class "Default")
      (node (ref "CQ") (pin "1") (pinfunction "G_1") (pintype "unspecified"))
      (node (ref "CRG") (pin "2") (pinfunction "2_2") (pintype "input"))
      (node (ref "H5") (pin "9") (pinfunction "9_9") (pintype "unspecified"))
      (node (ref "J2") (pin "9") (pinfunction "D6/AIN0_9") (pintype "unspecified"))
      (node (ref "LED9") (pin "2") (pinfunction "A_2") (pintype "unspecified"))
    )
    (net (code "22") (name "D7") (class "Default")
      (node (ref "DQ") (pin "1") (pinfunction "G_1") (pintype "unspecified"))
      (node (ref "DRG") (pin "2") (pinfunction "2_2") (pintype "input"))
      (node (ref "H5") (pin "10") (pinfunction "10_10") (pintype "unspecified"))
      (node (ref "J2") (pin "10") (pinfunction "D7/AIN1_10") (pintype "unspecified"))
      (node (ref "LED4") (pin "2") (pinfunction "A_2") (pintype "unspecified"))
      (node (ref "OUT_7") (pin "1") (pinfunction "1_1") (pintype "unspecified"))
    )
    (net (code "23") (name "D8") (class "Default")
      (node (ref "EQ") (pin "1") (pinfunction "G_1") (pintype "unspecified"))
      (node (ref "ERG") (pin "2") (pinfunction "2_2") (pintype "input"))
      (node (ref "H5") (pin "11") (pinfunction "11_11") (pintype "unspecified"))
      (node (ref "J2") (pin "11") (pinfunction "D8/ICP_11") (pintype "unspecified"))
      (node (ref "LED5") (pin "2") (pinfunction "A_2") (pintype "unspecified"))
      (node (ref "OUT_8") (pin "1") (pinfunction "1_1") (pintype "unspecified"))
    )
    (net (code "24") (name "D9") (class "Default")
      (node (ref "FQ") (pin "1") (pinfunction "G_1") (pintype "unspecified"))
      (node (ref "FRG") (pin "2") (pinfunction "2_2") (pintype "input"))
      (node (ref "H5") (pin "12") (pinfunction "12_12") (pintype "unspecified"))
      (node (ref "J2") (pin "12") (pinfunction "D9/0C1_12") (pintype "unspecified"))
      (node (ref "LED6") (pin "2") (pinfunction "A_2") (pintype "unspecified"))
      (node (ref "OUT_9") (pin "1") (pinfunction "1_1") (pintype "unspecified"))
    )
    (net (code "25") (name "D10") (class "Default")
      (node (ref "GQ") (pin "1") (pinfunction "G_1") (pintype "unspecified"))
      (node (ref "GRG") (pin "2") (pinfunction "2_2") (pintype "input"))
      (node (ref "H5") (pin "13") (pinfunction "13_13") (pintype "unspecified"))
      (node (ref "J2") (pin "13") (pinfunction "D10_13") (pintype "unspecified"))
      (node (ref "LED7") (pin "2") (pinfunction "A_2") (pintype "unspecified"))
      (node (ref "OUT_10") (pin "1") (pinfunction "1_1") (pintype "unspecified"))
    )
    (net (code "26") (name "D11") (class "Default")
      (node (ref "H5") (pin "14") (pinfunction "14_14") (pintype "unspecified"))
      (node (ref "HQ") (pin "1") (pinfunction "G_1") (pintype "unspecified"))
      (node (ref "HRG") (pin "2") (pinfunction "2_2") (pintype "input"))
      (node (ref "J2") (pin "14") (pinfunction "D11/MOSI_14") (pintype "unspecified"))
      (node (ref "LED8") (pin "2") (pinfunction "A_2") (pintype "unspecified"))
      (node (ref "OUT_11") (pin "1") (pinfunction "1_1") (pintype "unspecified"))
    )
    (net (code "27") (name "D13") (class "Default")
      (node (ref "H4") (pin "15") (pinfunction "15_15") (pintype "unspecified"))
      (node (ref "J2") (pin "16") (pinfunction "SCK/D13_16") (pintype "unspecified"))
    )
    (net (code "28") (name "GND") (class "Default")
      (node (ref "AQ") (pin "2") (pinfunction "S_2") (pintype "unspecified"))
      (node (ref "ARG") (pin "1") (pinfunction "1_1") (pintype "input"))
      (node (ref "ARL") (pin "1") (pinfunction "1_1") (pintype "input"))
      (node (ref "BQ") (pin "2") (pinfunction "S_2") (pintype "unspecified"))
      (node (ref "BRG") (pin "1") (pinfunction "1_1") (pintype "input"))
      (node (ref "BRL") (pin "1") (pinfunction "1_1") (pintype "input"))
      (node (ref "BUZZER1") (pin "2") (pinfunction "2_2") (pintype "unspecified"))
      (node (ref "C1") (pin "2") (pinfunction "2_2") (pintype "input"))
      (node (ref "C10") (pin "1") (pinfunction "1_1") (pintype "unspecified"))
      (node (ref "C11") (pin "1") (pinfunction "1_1") (pintype "unspecified"))
      (node (ref "C2") (pin "2") (pinfunction "2_2") (pintype "input"))
      (node (ref "C3") (pin "1") (pinfunction "1_1") (pintype "unspecified"))
      (node (ref "CQ") (pin "2") (pinfunction "S_2") (pintype "unspecified"))
      (node (ref "CRG") (pin "1") (pinfunction "1_1") (pintype "input"))
      (node (ref "CRL") (pin "1") (pinfunction "1_1") (pintype "input"))
      (node (ref "DC1") (pin "2") (pinfunction "2_2") (pintype "unspecified"))
      (node (ref "DC1") (pin "3") (pinfunction "3_3") (pintype "unspecified"))
      (node (ref "DDM1") (pin "2") (pinfunction "A_2") (pintype "unspecified"))
      (node (ref "DQ") (pin "2") (pinfunction "S_2") (pintype "unspecified"))
      (node (ref "DRG") (pin "1") (pinfunction "1_1") (pintype "input"))
      (node (ref "DRL") (pin "1") (pinfunction "1_1") (pintype "input"))
      (node (ref "EQ") (pin "2") (pinfunction "S_2") (pintype "unspecified"))
      (node (ref "ERG") (pin "1") (pinfunction "1_1") (pintype "input"))
      (node (ref "ERL") (pin "1") (pinfunction "1_1") (pintype "input"))
      (node (ref "FQ") (pin "2") (pinfunction "S_2") (pintype "unspecified"))
      (node (ref "FRG") (pin "1") (pinfunction "1_1") (pintype "input"))
      (node (ref "FRL") (pin "1") (pinfunction "1_1") (pintype "input"))
      (node (ref "GQ") (pin "2") (pinfunction "S_2") (pintype "unspecified"))
      (node (ref "GRG") (pin "1") (pinfunction "1_1") (pintype "input"))
      (node (ref "GRL") (pin "1") (pinfunction "1_1") (pintype "input"))
      (node (ref "H1") (pin "6") (pinfunction "6_6") (pintype "input"))
      (node (ref "H11") (pin "6") (pinfunction "6_6") (pintype "input"))
      (node (ref "H2") (pin "6") (pinfunction "6_6") (pintype "input"))
      (node (ref "H3") (pin "6") (pinfunction "6_6") (pintype "input"))
      (node (ref "H4") (pin "2") (pinfunction "2_2") (pintype "unspecified"))
      (node (ref "H5") (pin "4") (pinfunction "4_4") (pintype "unspecified"))
      (node (ref "H6") (pin "6") (pinfunction "6_6") (pintype "input"))
      (node (ref "HQ") (pin "2") (pinfunction "S_2") (pintype "unspecified"))
      (node (ref "HRG") (pin "1") (pinfunction "1_1") (pintype "input"))
      (node (ref "HRL") (pin "1") (pinfunction "1_1") (pintype "input"))
      (node (ref "J2") (pin "29") (pinfunction "GND_29") (pintype "unspecified"))
      (node (ref "J2") (pin "4") (pinfunction "GND_4") (pintype "unspecified"))
      (node (ref "OLED") (pin "2") (pinfunction "GND_2") (pintype "passive"))
      (node (ref "OUT_10") (pin "2") (pinfunction "2_2") (pintype "unspecified"))
      (node (ref "OUT_11") (pin "2") (pinfunction "2_2") (pintype "unspecified"))
      (node (ref "OUT_7") (pin "2") (pinfunction "2_2") (pintype "unspecified"))
      (node (ref "OUT_8") (pin "2") (pinfunction "2_2") (pintype "unspecified"))
      (node (ref "OUT_9") (pin "2") (pinfunction "2_2") (pintype "unspecified"))
      (node (ref "P6") (pin "1") (pinfunction "1_1") (pintype "unspecified"))
      (node (ref "P7") (pin "1") (pinfunction "1_1") (pintype "unspecified"))
      (node (ref "RL12V") (pin "2") (pinfunction "2_2") (pintype "input"))
      (node (ref "SENS_2") (pin "3") (pinfunction "3_3") (pintype "unspecified"))
      (node (ref "SENS_3") (pin "3") (pinfunction "3_3") (pintype "unspecified"))
      (node (ref "SENS_A1") (pin "3") (pinfunction "3_3") (pintype "unspecified"))
      (node (ref "SENS_A2") (pin "3") (pinfunction "3_3") (pintype "unspecified"))
      (node (ref "SENS_A3") (pin "3") (pinfunction "3_3") (pintype "unspecified"))
      (node (ref "SW2") (pin "3") (pinfunction "3_3") (pintype "unspecified"))
      (node (ref "SW2") (pin "4") (pinfunction "4_4") (pintype "unspecified"))
      (node (ref "SW3") (pin "3") (pinfunction "3_3") (pintype "unspecified"))
      (node (ref "SW3") (pin "4") (pinfunction "4_4") (pintype "unspecified"))
      (node (ref "SWA1") (pin "3") (pinfunction "3_3") (pintype "unspecified"))
      (node (ref "SWA1") (pin "4") (pinfunction "4_4") (pintype "unspecified"))
      (node (ref "SWA2") (pin "3") (pinfunction "3_3") (pintype "unspecified"))
      (node (ref "SWA2") (pin "4") (pinfunction "4_4") (pintype "unspecified"))
      (node (ref "SWA3") (pin "3") (pinfunction "3_3") (pintype "unspecified"))
      (node (ref "SWA3") (pin "4") (pinfunction "4_4") (pintype "unspecified"))
      (node (ref "U2") (pin "5") (pinfunction "GND_5") (pintype "unspecified"))
      (node (ref "U5") (pin "2") (pinfunction "GND_2") (pintype "unspecified"))
      (node (ref "VALVE-CON") (pin "2") (pinfunction "2_2") (pintype "unspecified"))
    )
    (net (code "29") (name "Net-(AQ-D)") (class "Default")
      (node (ref "AQ") (pin "3") (pinfunction "D_3") (pintype "unspecified"))
      (node (ref "DDM2") (pin "2") (pinfunction "A_2") (pintype "unspecified"))
      (node (ref "IGNIT_CON") (pin "2") (pinfunction "2_2") (pintype "unspecified"))
    )
    (net (code "30") (name "Net-(BQ-D)") (class "Default")
      (node (ref "BQ") (pin "3") (pinfunction "D_3") (pintype "unspecified"))
      (node (ref "D7") (pin "2") (pinfunction "A_2") (pintype "unspecified"))
      (node (ref "RLY4") (pin "3") (pinfunction "3_3") (pintype "unspecified"))
    )
    (net (code "31") (name "Net-(CQ-D)") (class "Default")
      (node (ref "CQ") (pin "3") (pinfunction "D_3") (pintype "unspecified"))
      (node (ref "D1") (pin "2") (pinfunction "A_2") (pintype "unspecified"))
      (node (ref "RLY1") (pin "4") (pinfunction "4_4") (pintype "unspecified"))
    )
    (net (code "32") (name "Net-(DDM-A)") (class "Default")
      (node (ref "DCM") (pin "2") (pinfunction "2_2") (pintype "input"))
      (node (ref "DCON") (pin "2") (pinfunction "2_2") (pintype "unspecified"))
      (node (ref "DDM") (pin "2") (pinfunction "A_2") (pintype "unspecified"))
      (node (ref "DQ") (pin "3") (pinfunction "D_3") (pintype "unspecified"))
    )
    (net (code "33") (name "Net-(DDM1-C)") (class "Default")
      (node (ref "DDM1") (pin "1") (pinfunction "C_1") (pintype "unspecified"))
      (node (ref "RLY4") (pin "2") (pinfunction "2_2") (pintype "unspecified"))
      (node (ref "VALVE-CON") (pin "1") (pinfunction "1_1") (pintype "unspecified"))
    )
    (net (code "34") (name "Net-(DDM2-C)") (class "Default")
      (node (ref "DDM2") (pin "1") (pinfunction "C_1") (pintype "unspecified"))
      (node (ref "IGNIT_CON") (pin "1") (pinfunction "1_1") (pintype "unspecified"))
      (node (ref "RLY4") (pin "1") (pinfunction "1_1") (pintype "unspecified"))
    )
    (net (code "35") (name "Net-(EDM-A)") (class "Default")
      (node (ref "ECM") (pin "2") (pinfunction "2_2") (pintype "input"))
      (node (ref "ECON") (pin "2") (pinfunction "2_2") (pintype "unspecified"))
      (node (ref "EDM") (pin "2") (pinfunction "A_2") (pintype "unspecified"))
      (node (ref "EQ") (pin "3") (pinfunction "D_3") (pintype "unspecified"))
    )
    (net (code "36") (name "Net-(FDM-A)") (class "Default")
      (node (ref "FCM") (pin "2") (pinfunction "2_2") (pintype "input"))
      (node (ref "FCON") (pin "2") (pinfunction "2_2") (pintype "unspecified"))
      (node (ref "FDM") (pin "2") (pinfunction "A_2") (pintype "unspecified"))
      (node (ref "FQ") (pin "3") (pinfunction "D_3") (pintype "unspecified"))
    )
    (net (code "37") (name "Net-(GDM-A)") (class "Default")
      (node (ref "GCM") (pin "2") (pinfunction "2_2") (pintype "input"))
      (node (ref "GCON") (pin "2") (pinfunction "2_2") (pintype "unspecified"))
      (node (ref "GDM") (pin "2") (pinfunction "A_2") (pintype "unspecified"))
      (node (ref "GQ") (pin "3") (pinfunction "D_3") (pintype "unspecified"))
    )
    (net (code "38") (name "Net-(H4-Pad3)") (class "Default")
      (node (ref "H4") (pin "3") (pinfunction "3_3") (pintype "unspecified"))
      (node (ref "J2") (pin "28") (pinfunction "RESET_28") (pintype "unspecified"))
    )
    (net (code "39") (name "Net-(H5-Pad3)") (class "Default")
      (node (ref "H5") (pin "3") (pinfunction "3_3") (pintype "unspecified"))
      (node (ref "J2") (pin "3") (pinfunction "RESET_3") (pintype "unspecified"))
    )
    (net (code "40") (name "Net-(HDM-A)") (class "Default")
      (node (ref "HCM") (pin "2") (pinfunction "2_2") (pintype "input"))
      (node (ref "HCON") (pin "2") (pinfunction "2_2") (pintype "unspecified"))
      (node (ref "HDM") (pin "2") (pinfunction "A_2") (pintype "unspecified"))
      (node (ref "HQ") (pin "3") (pinfunction "D_3") (pintype "unspecified"))
    )
    (net (code "41") (name "Net-(J2-AREF)") (class "Default")
      (node (ref "H4") (pin "13") (pinfunction "13_13") (pintype "unspecified"))
      (node (ref "J2") (pin "18") (pinfunction "AREF_18") (pintype "unspecified"))
    )
    (net (code "42") (name "Net-(LED1-K)") (class "Default")
      (node (ref "LED1") (pin "1") (pinfunction "K_1") (pintype "unspecified"))
      (node (ref "RL12V") (pin "1") (pinfunction "1_1") (pintype "input"))
    )
    (net (code "43") (name "Net-(LED2-K)") (class "Default")
      (node (ref "ARL") (pin "2") (pinfunction "2_2") (pintype "input"))
      (node (ref "LED2") (pin "2") (pinfunction "K_2") (pintype "unspecified"))
    )
    (net (code "44") (name "Net-(LED3-C)") (class "Default")
      (node (ref "BRL") (pin "2") (pinfunction "2_2") (pintype "input"))
      (node (ref "LED3") (pin "1") (pinfunction "C_1") (pintype "input"))
    )
    (net (code "45") (name "Net-(LED4-K)") (class "Default")
      (node (ref "DRL") (pin "2") (pinfunction "2_2") (pintype "input"))
      (node (ref "LED4") (pin "1") (pinfunction "K_1") (pintype "unspecified"))
    )
    (net (code "46") (name "Net-(LED5-K)") (class "Default")
      (node (ref "ERL") (pin "2") (pinfunction "2_2") (pintype "input"))
      (node (ref "LED5") (pin "1") (pinfunction "K_1") (pintype "unspecified"))
    )
    (net (code "47") (name "Net-(LED6-K)") (class "Default")
      (node (ref "FRL") (pin "2") (pinfunction "2_2") (pintype "input"))
      (node (ref "LED6") (pin "1") (pinfunction "K_1") (pintype "unspecified"))
    )
    (net (code "48") (name "Net-(LED7-K)") (class "Default")
      (node (ref "GRL") (pin "2") (pinfunction "2_2") (pintype "input"))
      (node (ref "LED7") (pin "1") (pinfunction "K_1") (pintype "unspecified"))
    )
    (net (code "49") (name "Net-(LED8-K)") (class "Default")
      (node (ref "HRL") (pin "2") (pinfunction "2_2") (pintype "input"))
      (node (ref "LED8") (pin "1") (pinfunction "K_1") (pintype "unspecified"))
    )
    (net (code "50") (name "Net-(LED9-K)") (class "Default")
      (node (ref "CRL") (pin "2") (pinfunction "2_2") (pintype "input"))
      (node (ref "LED9") (pin "1") (pinfunction "K_1") (pintype "unspecified"))
    )
    (net (code "51") (name "Net-(RLY1-Pad1)") (class "Default")
      (node (ref "RLY1") (pin "1") (pinfunction "1_1") (pintype "unspecified"))
      (node (ref "XT_M") (pin "1") (pinfunction "1_1") (pintype "unspecified"))
    )
    (net (code "52") (name "Net-(RLY1-Pad2)") (class "Default")
      (node (ref "RLY1") (pin "2") (pinfunction "2_2") (pintype "unspecified"))
      (node (ref "XT_M1") (pin "1") (pinfunction "1_1") (pintype "unspecified"))
    )
    (net (code "53") (name "Net-(RLY1-Pad5)") (class "Default")
      (node (ref "RLY1") (pin "5") (pinfunction "5_5") (pintype "unspecified"))
      (node (ref "U2") (pin "1") (pinfunction "IP+_1") (pintype "unspecified"))
      (node (ref "U2") (pin "2") (pinfunction "IP+_2") (pintype "unspecified"))
    )
    (net (code "54") (name "Net-(U2-FILTER)") (class "Default")
      (node (ref "C3") (pin "2") (pinfunction "2_2") (pintype "unspecified"))
      (node (ref "U2") (pin "6") (pinfunction "FILTER_6") (pintype "unspecified"))
    )
    (net (code "55") (name "Net-(XT_F-+)") (class "Default")
      (node (ref "U2") (pin "3") (pinfunction "IP-_3") (pintype "unspecified"))
      (node (ref "U2") (pin "4") (pinfunction "IP-_4") (pintype "unspecified"))
      (node (ref "XT_F") (pin "2") (pinfunction "+_2") (pintype "unspecified"))
    )
    (net (code "56") (name "Net-(XT_F--)") (class "Default")
      (node (ref "XT_F") (pin "1") (pinfunction "-_1") (pintype "unspecified"))
      (node (ref "XT_M") (pin "2") (pinfunction "2_2") (pintype "unspecified"))
      (node (ref "XT_M1") (pin "2") (pinfunction "2_2") (pintype "unspecified"))
    )
    (net (code "58") (name "unconnected-(H1-Pad2)") (class "Default")
      (node (ref "H1") (pin "2") (pinfunction "2_2") (pintype "input"))
    )
    (net (code "59") (name "unconnected-(H1-Pad3)") (class "Default")
      (node (ref "H1") (pin "3") (pinfunction "3_3") (pintype "input"))
    )
    (net (code "60") (name "unconnected-(H1-Pad4)") (class "Default")
      (node (ref "H1") (pin "4") (pinfunction "4_4") (pintype "input"))
    )
    (net (code "61") (name "unconnected-(H1-Pad5)") (class "Default")
      (node (ref "H1") (pin "5") (pinfunction "5_5") (pintype "input"))
    )
    (net (code "62") (name "unconnected-(H2-Pad2)") (class "Default")
      (node (ref "H2") (pin "2") (pinfunction "2_2") (pintype "input"))
    )
    (net (code "63") (name "unconnected-(H2-Pad3)") (class "Default")
      (node (ref "H2") (pin "3") (pinfunction "3_3") (pintype "input"))
    )
    (net (code "64") (name "unconnected-(H2-Pad4)") (class "Default")
      (node (ref "H2") (pin "4") (pinfunction "4_4") (pintype "input"))
    )
    (net (code "65") (name "unconnected-(H2-Pad5)") (class "Default")
      (node (ref "H2") (pin "5") (pinfunction "5_5") (pintype "input"))
    )
    (net (code "66") (name "unconnected-(H3-Pad2)") (class "Default")
      (node (ref "H3") (pin "2") (pinfunction "2_2") (pintype "input"))
    )
    (net (code "67") (name "unconnected-(H3-Pad3)") (class "Default")
      (node (ref "H3") (pin "3") (pinfunction "3_3") (pintype "input"))
    )
    (net (code "68") (name "unconnected-(H3-Pad4)") (class "Default")
      (node (ref "H3") (pin "4") (pinfunction "4_4") (pintype "input"))
    )
    (net (code "69") (name "unconnected-(H3-Pad5)") (class "Default")
      (node (ref "H3") (pin "5") (pinfunction "5_5") (pintype "input"))
    )
    (net (code "70") (name "unconnected-(H6-Pad2)") (class "Default")
      (node (ref "H6") (pin "2") (pinfunction "2_2") (pintype "input"))
    )
    (net (code "71") (name "unconnected-(H6-Pad3)") (class "Default")
      (node (ref "H6") (pin "3") (pinfunction "3_3") (pintype "input"))
    )
    (net (code "72") (name "unconnected-(H6-Pad4)") (class "Default")
      (node (ref "H6") (pin "4") (pinfunction "4_4") (pintype "input"))
    )
    (net (code "73") (name "unconnected-(H6-Pad5)") (class "Default")
      (node (ref "H6") (pin "5") (pinfunction "5_5") (pintype "input"))
    )
    (net (code "74") (name "unconnected-(H11-Pad2)") (class "Default")
      (node (ref "H11") (pin "2") (pinfunction "2_2") (pintype "input"))
    )
    (net (code "75") (name "unconnected-(H11-Pad3)") (class "Default")
      (node (ref "H11") (pin "3") (pinfunction "3_3") (pintype "input"))
    )
    (net (code "76") (name "unconnected-(H11-Pad4)") (class "Default")
      (node (ref "H11") (pin "4") (pinfunction "4_4") (pintype "input"))
    )
    (net (code "77") (name "unconnected-(H11-Pad5)") (class "Default")
      (node (ref "H11") (pin "5") (pinfunction "5_5") (pintype "input"))
    )
  )
)
